# power_board.net
KiCad netlist of a schematic drawn in EAGLE
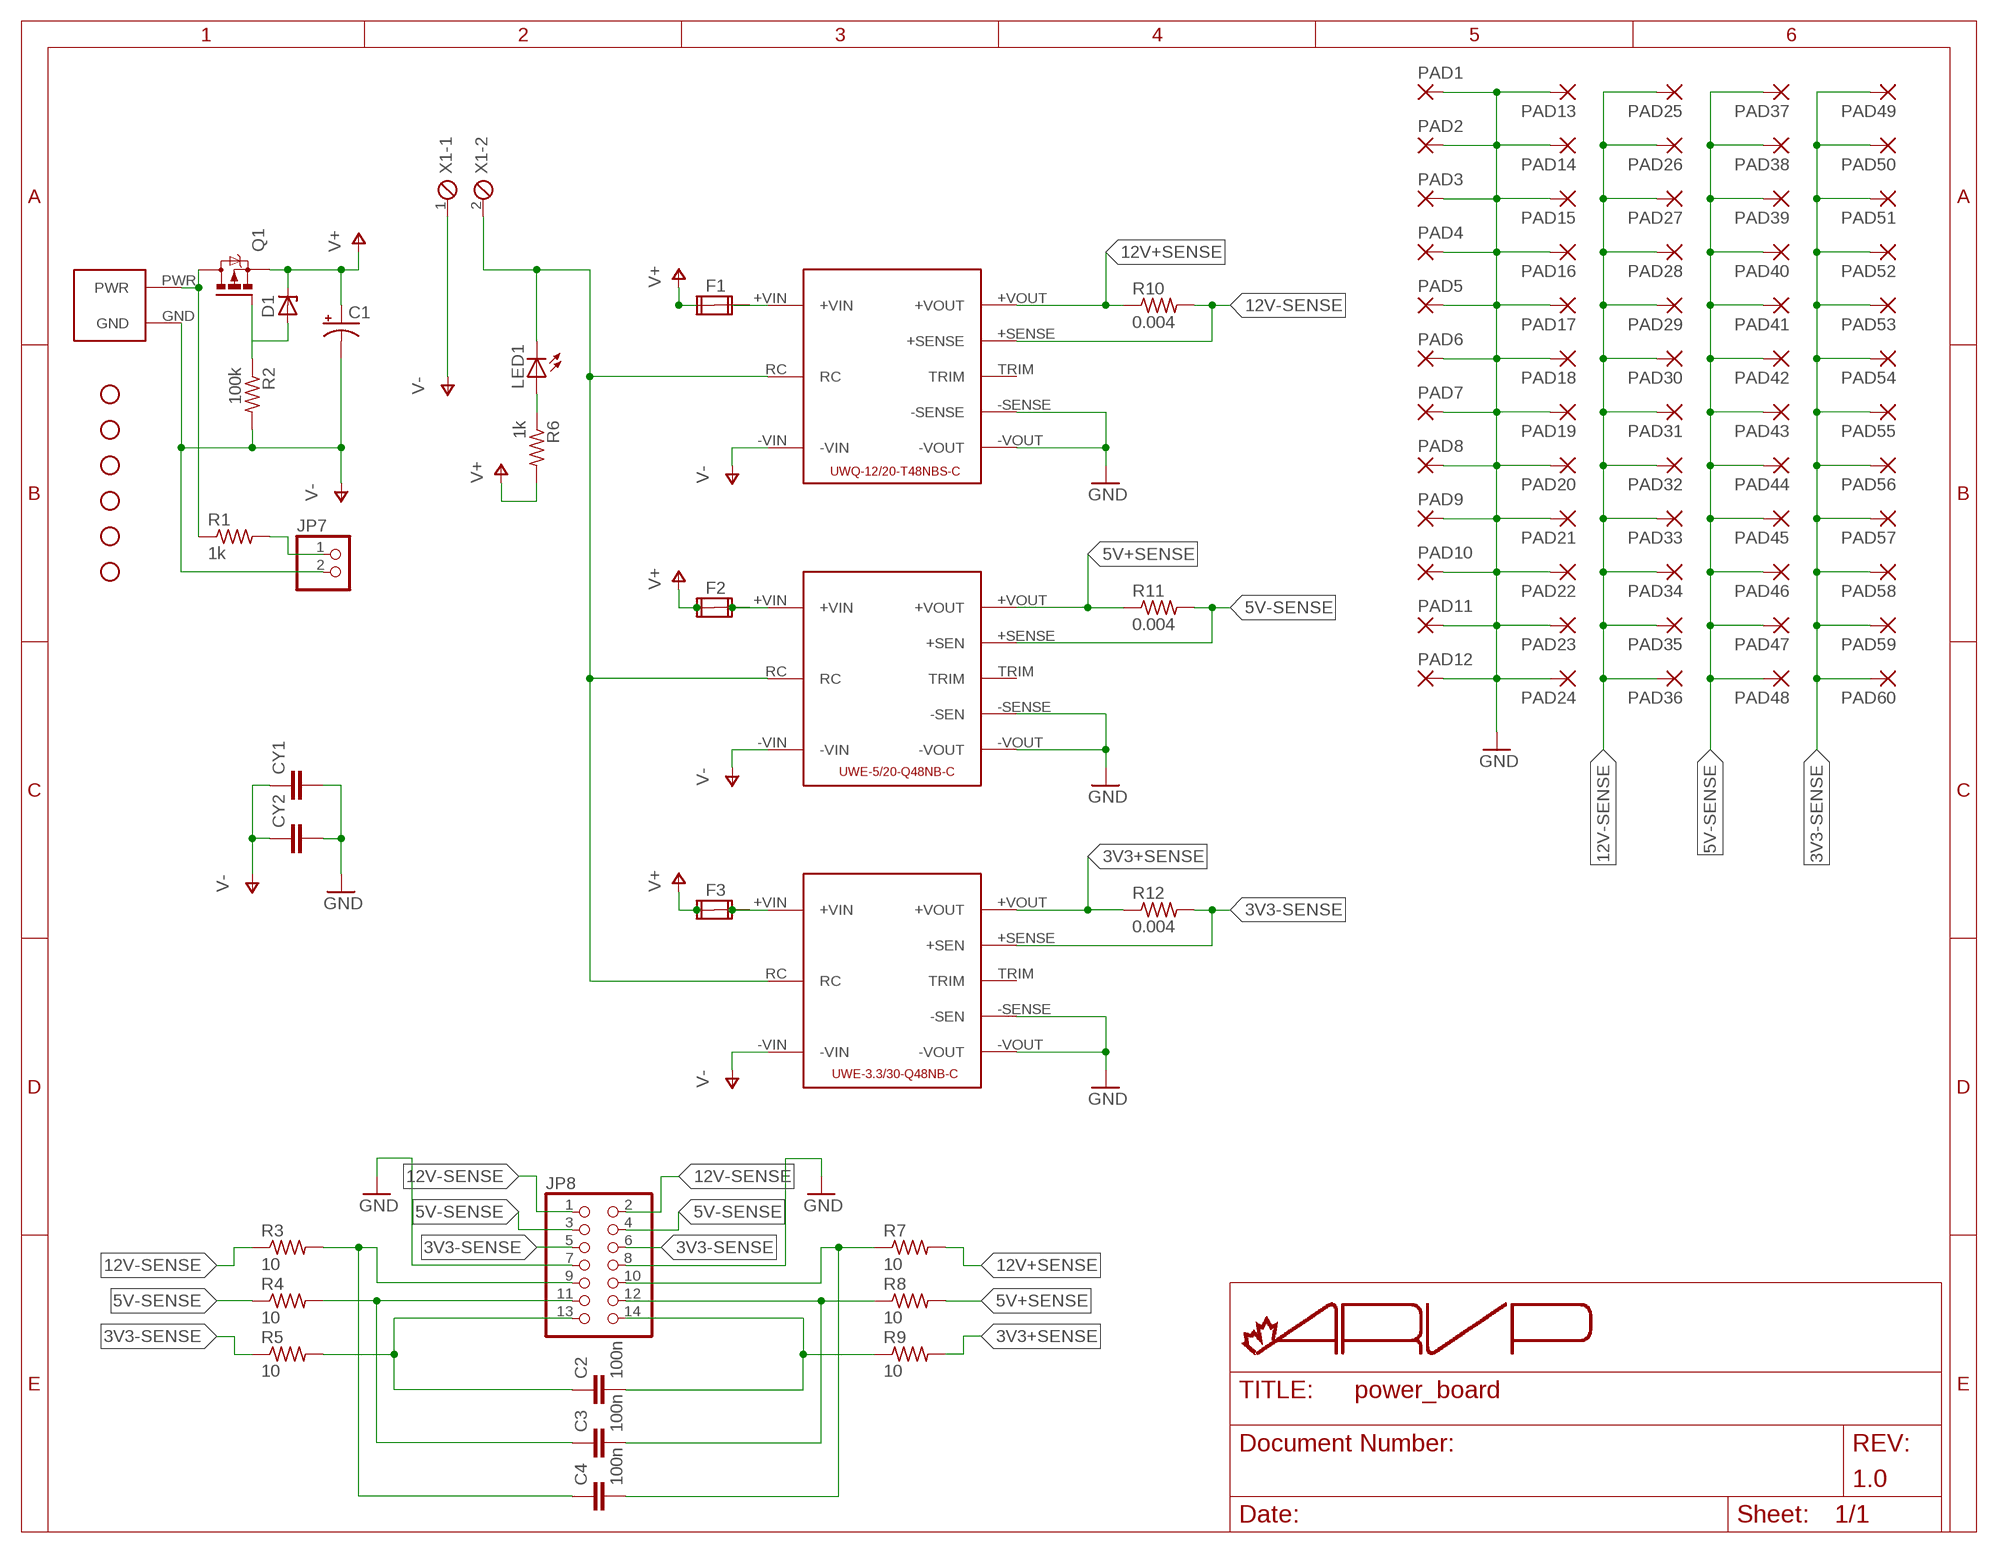
[diagram p0: schematic, sheet 1]

(export (version "E")
  (design (tool "Eeschema 10.0.6"))
  (components
    (comp (ref "C1")
      (value "CPOL-USE5-10.5")
      (footprint "eagle-import:E5-10,5")
      (libsource (lib "eagle-import") (part "CPOL-USE5-10.5"))
    )
    (comp (ref "C2")
      (value "100n")
      (footprint "eagle-import:C025-024X044")
      (libsource (lib "eagle-import") (part "C-EU025-024X044"))
    )
    (comp (ref "C3")
      (value "100n")
      (footprint "eagle-import:C025-024X044")
      (libsource (lib "eagle-import") (part "C-EU025-024X044"))
    )
    (comp (ref "C4")
      (value "100n")
      (footprint "eagle-import:C025-024X044")
      (libsource (lib "eagle-import") (part "C-EU025-024X044"))
    )
    (comp (ref "CY1")
      (value "CYYC7B5")
      (footprint "eagle-import:YC7B5")
      (libsource (lib "eagle-import") (part "CYYC7B5"))
    )
    (comp (ref "CY2")
      (value "CYYC7B5")
      (footprint "eagle-import:YC7B5")
      (libsource (lib "eagle-import") (part "CYYC7B5"))
    )
    (comp (ref "D1")
      (value "ZENER-DIODEDO35Z10")
      (footprint "eagle-import:DO35Z10")
      (libsource (lib "eagle-import") (part "ZENER-DIODEDO35Z10"))
    )
    (comp (ref "F1")
      (value "FUSE2P")
      (footprint "eagle-import:FUSE1")
      (libsource (lib "eagle-import") (part "FUSE2P"))
    )
    (comp (ref "F2")
      (value "FUSE2P")
      (footprint "eagle-import:FUSE1")
      (libsource (lib "eagle-import") (part "FUSE2P"))
    )
    (comp (ref "F3")
      (value "FUSE2P")
      (footprint "eagle-import:FUSE1")
      (libsource (lib "eagle-import") (part "FUSE2P"))
    )
    (comp (ref "JP1")
      (value "STAND-OFF")
      (footprint "eagle-import:STAND-OFF")
      (libsource (lib "eagle-import") (part "STAND-OFF"))
    )
    (comp (ref "JP2")
      (value "STAND-OFF")
      (footprint "eagle-import:STAND-OFF")
      (libsource (lib "eagle-import") (part "STAND-OFF"))
    )
    (comp (ref "JP3")
      (value "STAND-OFF")
      (footprint "eagle-import:STAND-OFF")
      (libsource (lib "eagle-import") (part "STAND-OFF"))
    )
    (comp (ref "JP4")
      (value "STAND-OFF")
      (footprint "eagle-import:STAND-OFF")
      (libsource (lib "eagle-import") (part "STAND-OFF"))
    )
    (comp (ref "JP5")
      (value "STAND-OFF")
      (footprint "eagle-import:STAND-OFF")
      (libsource (lib "eagle-import") (part "STAND-OFF"))
    )
    (comp (ref "JP6")
      (value "STAND-OFF")
      (footprint "eagle-import:STAND-OFF")
      (libsource (lib "eagle-import") (part "STAND-OFF"))
    )
    (comp (ref "JP7")
      (value "PINHD-1X2")
      (footprint "eagle-import:1X02")
      (libsource (lib "eagle-import") (part "PINHD-1X2"))
    )
    (comp (ref "JP8")
      (value "PINHD-2X7")
      (footprint "eagle-import:2X07")
      (libsource (lib "eagle-import") (part "PINHD-2X7"))
    )
    (comp (ref "LED1")
      (value "LED3MM")
      (footprint "eagle-import:LED3MM")
      (libsource (lib "eagle-import") (part "LED3MM"))
    )
    (comp (ref "P$1")
      (value "AND_PWR")
      (footprint "eagle-import:AND_PWR")
      (libsource (lib "eagle-import") (part "AND_PWR"))
    )
    (comp (ref "PAD1")
      (value "WIREPAD3,17/1,3")
      (footprint "eagle-import:3,17_1,3")
      (libsource (lib "eagle-import") (part "WIREPAD3,17/1,3"))
    )
    (comp (ref "PAD2")
      (value "WIREPAD3,17/1,3")
      (footprint "eagle-import:3,17_1,3")
      (libsource (lib "eagle-import") (part "WIREPAD3,17/1,3"))
    )
    (comp (ref "PAD3")
      (value "WIREPAD3,17/1,3")
      (footprint "eagle-import:3,17_1,3")
      (libsource (lib "eagle-import") (part "WIREPAD3,17/1,3"))
    )
    (comp (ref "PAD4")
      (value "WIREPAD3,17/1,3")
      (footprint "eagle-import:3,17_1,3")
      (libsource (lib "eagle-import") (part "WIREPAD3,17/1,3"))
    )
    (comp (ref "PAD5")
      (value "WIREPAD3,17/1,3")
      (footprint "eagle-import:3,17_1,3")
      (libsource (lib "eagle-import") (part "WIREPAD3,17/1,3"))
    )
    (comp (ref "PAD6")
      (value "WIREPAD3,17/1,3")
      (footprint "eagle-import:3,17_1,3")
      (libsource (lib "eagle-import") (part "WIREPAD3,17/1,3"))
    )
    (comp (ref "PAD7")
      (value "WIREPAD3,17/1,3")
      (footprint "eagle-import:3,17_1,3")
      (libsource (lib "eagle-import") (part "WIREPAD3,17/1,3"))
    )
    (comp (ref "PAD8")
      (value "WIREPAD3,17/1,3")
      (footprint "eagle-import:3,17_1,3")
      (libsource (lib "eagle-import") (part "WIREPAD3,17/1,3"))
    )
    (comp (ref "PAD9")
      (value "WIREPAD3,17/1,3")
      (footprint "eagle-import:3,17_1,3")
      (libsource (lib "eagle-import") (part "WIREPAD3,17/1,3"))
    )
    (comp (ref "PAD10")
      (value "WIREPAD3,17/1,3")
      (footprint "eagle-import:3,17_1,3")
      (libsource (lib "eagle-import") (part "WIREPAD3,17/1,3"))
    )
    (comp (ref "PAD11")
      (value "WIREPAD3,17/1,3")
      (footprint "eagle-import:3,17_1,3")
      (libsource (lib "eagle-import") (part "WIREPAD3,17/1,3"))
    )
    (comp (ref "PAD12")
      (value "WIREPAD3,17/1,3")
      (footprint "eagle-import:3,17_1,3")
      (libsource (lib "eagle-import") (part "WIREPAD3,17/1,3"))
    )
    (comp (ref "PAD13")
      (value "WIREPAD3,17/1,3")
      (footprint "eagle-import:3,17_1,3")
      (libsource (lib "eagle-import") (part "WIREPAD3,17/1,3"))
    )
    (comp (ref "PAD14")
      (value "WIREPAD3,17/1,3")
      (footprint "eagle-import:3,17_1,3")
      (libsource (lib "eagle-import") (part "WIREPAD3,17/1,3"))
    )
    (comp (ref "PAD15")
      (value "WIREPAD3,17/1,3")
      (footprint "eagle-import:3,17_1,3")
      (libsource (lib "eagle-import") (part "WIREPAD3,17/1,3"))
    )
    (comp (ref "PAD16")
      (value "WIREPAD3,17/1,3")
      (footprint "eagle-import:3,17_1,3")
      (libsource (lib "eagle-import") (part "WIREPAD3,17/1,3"))
    )
    (comp (ref "PAD17")
      (value "WIREPAD3,17/1,3")
      (footprint "eagle-import:3,17_1,3")
      (libsource (lib "eagle-import") (part "WIREPAD3,17/1,3"))
    )
    (comp (ref "PAD18")
      (value "WIREPAD3,17/1,3")
      (footprint "eagle-import:3,17_1,3")
      (libsource (lib "eagle-import") (part "WIREPAD3,17/1,3"))
    )
    (comp (ref "PAD19")
      (value "WIREPAD3,17/1,3")
      (footprint "eagle-import:3,17_1,3")
      (libsource (lib "eagle-import") (part "WIREPAD3,17/1,3"))
    )
    (comp (ref "PAD20")
      (value "WIREPAD3,17/1,3")
      (footprint "eagle-import:3,17_1,3")
      (libsource (lib "eagle-import") (part "WIREPAD3,17/1,3"))
    )
    (comp (ref "PAD21")
      (value "WIREPAD3,17/1,3")
      (footprint "eagle-import:3,17_1,3")
      (libsource (lib "eagle-import") (part "WIREPAD3,17/1,3"))
    )
    (comp (ref "PAD22")
      (value "WIREPAD3,17/1,3")
      (footprint "eagle-import:3,17_1,3")
      (libsource (lib "eagle-import") (part "WIREPAD3,17/1,3"))
    )
    (comp (ref "PAD23")
      (value "WIREPAD3,17/1,3")
      (footprint "eagle-import:3,17_1,3")
      (libsource (lib "eagle-import") (part "WIREPAD3,17/1,3"))
    )
    (comp (ref "PAD24")
      (value "WIREPAD3,17/1,3")
      (footprint "eagle-import:3,17_1,3")
      (libsource (lib "eagle-import") (part "WIREPAD3,17/1,3"))
    )
    (comp (ref "PAD25")
      (value "WIREPAD3,17/1,3")
      (footprint "eagle-import:3,17_1,3")
      (libsource (lib "eagle-import") (part "WIREPAD3,17/1,3"))
    )
    (comp (ref "PAD26")
      (value "WIREPAD3,17/1,3")
      (footprint "eagle-import:3,17_1,3")
      (libsource (lib "eagle-import") (part "WIREPAD3,17/1,3"))
    )
    (comp (ref "PAD27")
      (value "WIREPAD3,17/1,3")
      (footprint "eagle-import:3,17_1,3")
      (libsource (lib "eagle-import") (part "WIREPAD3,17/1,3"))
    )
    (comp (ref "PAD28")
      (value "WIREPAD3,17/1,3")
      (footprint "eagle-import:3,17_1,3")
      (libsource (lib "eagle-import") (part "WIREPAD3,17/1,3"))
    )
    (comp (ref "PAD29")
      (value "WIREPAD3,17/1,3")
      (footprint "eagle-import:3,17_1,3")
      (libsource (lib "eagle-import") (part "WIREPAD3,17/1,3"))
    )
    (comp (ref "PAD30")
      (value "WIREPAD3,17/1,3")
      (footprint "eagle-import:3,17_1,3")
      (libsource (lib "eagle-import") (part "WIREPAD3,17/1,3"))
    )
    (comp (ref "PAD31")
      (value "WIREPAD3,17/1,3")
      (footprint "eagle-import:3,17_1,3")
      (libsource (lib "eagle-import") (part "WIREPAD3,17/1,3"))
    )
    (comp (ref "PAD32")
      (value "WIREPAD3,17/1,3")
      (footprint "eagle-import:3,17_1,3")
      (libsource (lib "eagle-import") (part "WIREPAD3,17/1,3"))
    )
    (comp (ref "PAD33")
      (value "WIREPAD3,17/1,3")
      (footprint "eagle-import:3,17_1,3")
      (libsource (lib "eagle-import") (part "WIREPAD3,17/1,3"))
    )
    (comp (ref "PAD34")
      (value "WIREPAD3,17/1,3")
      (footprint "eagle-import:3,17_1,3")
      (libsource (lib "eagle-import") (part "WIREPAD3,17/1,3"))
    )
    (comp (ref "PAD35")
      (value "WIREPAD3,17/1,3")
      (footprint "eagle-import:3,17_1,3")
      (libsource (lib "eagle-import") (part "WIREPAD3,17/1,3"))
    )
    (comp (ref "PAD36")
      (value "WIREPAD3,17/1,3")
      (footprint "eagle-import:3,17_1,3")
      (libsource (lib "eagle-import") (part "WIREPAD3,17/1,3"))
    )
    (comp (ref "PAD37")
      (value "WIREPAD3,17/1,3")
      (footprint "eagle-import:3,17_1,3")
      (libsource (lib "eagle-import") (part "WIREPAD3,17/1,3"))
    )
    (comp (ref "PAD38")
      (value "WIREPAD3,17/1,3")
      (footprint "eagle-import:3,17_1,3")
      (libsource (lib "eagle-import") (part "WIREPAD3,17/1,3"))
    )
    (comp (ref "PAD39")
      (value "WIREPAD3,17/1,3")
      (footprint "eagle-import:3,17_1,3")
      (libsource (lib "eagle-import") (part "WIREPAD3,17/1,3"))
    )
    (comp (ref "PAD40")
      (value "WIREPAD3,17/1,3")
      (footprint "eagle-import:3,17_1,3")
      (libsource (lib "eagle-import") (part "WIREPAD3,17/1,3"))
    )
    (comp (ref "PAD41")
      (value "WIREPAD3,17/1,3")
      (footprint "eagle-import:3,17_1,3")
      (libsource (lib "eagle-import") (part "WIREPAD3,17/1,3"))
    )
    (comp (ref "PAD42")
      (value "WIREPAD3,17/1,3")
      (footprint "eagle-import:3,17_1,3")
      (libsource (lib "eagle-import") (part "WIREPAD3,17/1,3"))
    )
    (comp (ref "PAD43")
      (value "WIREPAD3,17/1,3")
      (footprint "eagle-import:3,17_1,3")
      (libsource (lib "eagle-import") (part "WIREPAD3,17/1,3"))
    )
    (comp (ref "PAD44")
      (value "WIREPAD3,17/1,3")
      (footprint "eagle-import:3,17_1,3")
      (libsource (lib "eagle-import") (part "WIREPAD3,17/1,3"))
    )
    (comp (ref "PAD45")
      (value "WIREPAD3,17/1,3")
      (footprint "eagle-import:3,17_1,3")
      (libsource (lib "eagle-import") (part "WIREPAD3,17/1,3"))
    )
    (comp (ref "PAD46")
      (value "WIREPAD3,17/1,3")
      (footprint "eagle-import:3,17_1,3")
      (libsource (lib "eagle-import") (part "WIREPAD3,17/1,3"))
    )
    (comp (ref "PAD47")
      (value "WIREPAD3,17/1,3")
      (footprint "eagle-import:3,17_1,3")
      (libsource (lib "eagle-import") (part "WIREPAD3,17/1,3"))
    )
    (comp (ref "PAD48")
      (value "WIREPAD3,17/1,3")
      (footprint "eagle-import:3,17_1,3")
      (libsource (lib "eagle-import") (part "WIREPAD3,17/1,3"))
    )
    (comp (ref "PAD49")
      (value "WIREPAD3,17/1,3")
      (footprint "eagle-import:3,17_1,3")
      (libsource (lib "eagle-import") (part "WIREPAD3,17/1,3"))
    )
    (comp (ref "PAD50")
      (value "WIREPAD3,17/1,3")
      (footprint "eagle-import:3,17_1,3")
      (libsource (lib "eagle-import") (part "WIREPAD3,17/1,3"))
    )
    (comp (ref "PAD51")
      (value "WIREPAD3,17/1,3")
      (footprint "eagle-import:3,17_1,3")
      (libsource (lib "eagle-import") (part "WIREPAD3,17/1,3"))
    )
    (comp (ref "PAD52")
      (value "WIREPAD3,17/1,3")
      (footprint "eagle-import:3,17_1,3")
      (libsource (lib "eagle-import") (part "WIREPAD3,17/1,3"))
    )
    (comp (ref "PAD53")
      (value "WIREPAD3,17/1,3")
      (footprint "eagle-import:3,17_1,3")
      (libsource (lib "eagle-import") (part "WIREPAD3,17/1,3"))
    )
    (comp (ref "PAD54")
      (value "WIREPAD3,17/1,3")
      (footprint "eagle-import:3,17_1,3")
      (libsource (lib "eagle-import") (part "WIREPAD3,17/1,3"))
    )
    (comp (ref "PAD55")
      (value "WIREPAD3,17/1,3")
      (footprint "eagle-import:3,17_1,3")
      (libsource (lib "eagle-import") (part "WIREPAD3,17/1,3"))
    )
    (comp (ref "PAD56")
      (value "WIREPAD3,17/1,3")
      (footprint "eagle-import:3,17_1,3")
      (libsource (lib "eagle-import") (part "WIREPAD3,17/1,3"))
    )
    (comp (ref "PAD57")
      (value "WIREPAD3,17/1,3")
      (footprint "eagle-import:3,17_1,3")
      (libsource (lib "eagle-import") (part "WIREPAD3,17/1,3"))
    )
    (comp (ref "PAD58")
      (value "WIREPAD3,17/1,3")
      (footprint "eagle-import:3,17_1,3")
      (libsource (lib "eagle-import") (part "WIREPAD3,17/1,3"))
    )
    (comp (ref "PAD59")
      (value "WIREPAD3,17/1,3")
      (footprint "eagle-import:3,17_1,3")
      (libsource (lib "eagle-import") (part "WIREPAD3,17/1,3"))
    )
    (comp (ref "PAD60")
      (value "WIREPAD3,17/1,3")
      (footprint "eagle-import:3,17_1,3")
      (libsource (lib "eagle-import") (part "WIREPAD3,17/1,3"))
    )
    (comp (ref "Q1")
      (value "IPP80P03P4L04AKSA1")
      (footprint "eagle-import:TO220BV")
      (libsource (lib "eagle-import") (part "IPP80P03P4L04AKSA1"))
    )
    (comp (ref "R1")
      (value "1k")
      (footprint "eagle-import:0204_7")
      (libsource (lib "eagle-import") (part "resistor_R-US_0204/7"))
    )
    (comp (ref "R2")
      (value "100k")
      (footprint "eagle-import:0204_7")
      (libsource (lib "eagle-import") (part "resistor_R-US_0204/7"))
    )
    (comp (ref "R3")
      (value "10")
      (footprint "eagle-import:0204_5")
      (libsource (lib "eagle-import") (part "R-US_0204/5"))
    )
    (comp (ref "R4")
      (value "10")
      (footprint "eagle-import:0204_5")
      (libsource (lib "eagle-import") (part "R-US_0204/5"))
    )
    (comp (ref "R5")
      (value "10")
      (footprint "eagle-import:0204_5")
      (libsource (lib "eagle-import") (part "R-US_0204/5"))
    )
    (comp (ref "R6")
      (value "1k")
      (footprint "eagle-import:0204_7")
      (libsource (lib "eagle-import") (part "resistor_R-US_0204/7"))
    )
    (comp (ref "R7")
      (value "10")
      (footprint "eagle-import:0204_5")
      (libsource (lib "eagle-import") (part "R-US_0204/5"))
    )
    (comp (ref "R8")
      (value "10")
      (footprint "eagle-import:0204_5")
      (libsource (lib "eagle-import") (part "R-US_0204/5"))
    )
    (comp (ref "R9")
      (value "10")
      (footprint "eagle-import:0204_5")
      (libsource (lib "eagle-import") (part "R-US_0204/5"))
    )
    (comp (ref "R10")
      (value "0.004")
      (footprint "eagle-import:0617_22")
      (libsource (lib "eagle-import") (part "R-US_0617/22"))
    )
    (comp (ref "R11")
      (value "0.004")
      (footprint "eagle-import:0617_22")
      (libsource (lib "eagle-import") (part "R-US_0617/22"))
    )
    (comp (ref "R12")
      (value "0.004")
      (footprint "eagle-import:0617_22")
      (libsource (lib "eagle-import") (part "R-US_0617/22"))
    )
    (comp (ref "U1")
      (value "UWQ-12/20-T48NBS-C")
      (footprint "eagle-import:UWQ-12_20-T48")
      (libsource (lib "eagle-import") (part "UWQ-12/20-T48NBS-C"))
    )
    (comp (ref "U2")
      (value "UWE-5/20-Q48NB-C")
      (footprint "eagle-import:UWE-100-120W")
      (libsource (lib "eagle-import") (part "UWE-5/20-Q48NB-C"))
    )
    (comp (ref "U3")
      (value "UWE-3.3/30-Q48NB-C")
      (footprint "eagle-import:UWE-100-120W")
      (libsource (lib "eagle-import") (part "UWE-3.3/30-Q48NB-C"))
    )
    (comp (ref "X1")
      (value "MPT2")
      (footprint "eagle-import:2POL254")
      (libsource (lib "eagle-import") (part "MPT2"))
    )
  )
  (nets
    (net (code "1") (name "3V3+SENSE") (class "Default")
      (node (ref "R12") (pin "1") (pinfunction "1_1") (pintype "passive"))
      (node (ref "R9") (pin "2") (pinfunction "2_2") (pintype "passive"))
      (node (ref "U3") (pin "+VOUT") (pinfunction "+VOUT_+VOUT") (pintype "power_in"))
    )
    (net (code "2") (name "3V3-SENSE") (class "Default")
      (node (ref "JP8") (pin "5") (pinfunction "5_5") (pintype "passive"))
      (node (ref "JP8") (pin "6") (pinfunction "6_6") (pintype "passive"))
      (node (ref "PAD49") (pin "1") (pinfunction "P_1") (pintype "passive"))
      (node (ref "PAD50") (pin "1") (pinfunction "P_1") (pintype "passive"))
      (node (ref "PAD51") (pin "1") (pinfunction "P_1") (pintype "passive"))
      (node (ref "PAD52") (pin "1") (pinfunction "P_1") (pintype "passive"))
      (node (ref "PAD53") (pin "1") (pinfunction "P_1") (pintype "passive"))
      (node (ref "PAD54") (pin "1") (pinfunction "P_1") (pintype "passive"))
      (node (ref "PAD55") (pin "1") (pinfunction "P_1") (pintype "passive"))
      (node (ref "PAD56") (pin "1") (pinfunction "P_1") (pintype "passive"))
      (node (ref "PAD57") (pin "1") (pinfunction "P_1") (pintype "passive"))
      (node (ref "PAD58") (pin "1") (pinfunction "P_1") (pintype "passive"))
      (node (ref "PAD59") (pin "1") (pinfunction "P_1") (pintype "passive"))
      (node (ref "PAD60") (pin "1") (pinfunction "P_1") (pintype "passive"))
      (node (ref "R12") (pin "2") (pinfunction "2_2") (pintype "passive"))
      (node (ref "R5") (pin "1") (pinfunction "1_1") (pintype "passive"))
      (node (ref "U3") (pin "+SENSE") (pinfunction "+SEN_+SENSE") (pintype "bidirectional"))
    )
    (net (code "3") (name "5V+SENSE") (class "Default")
      (node (ref "R11") (pin "1") (pinfunction "1_1") (pintype "passive"))
      (node (ref "R8") (pin "2") (pinfunction "2_2") (pintype "passive"))
      (node (ref "U2") (pin "+VOUT") (pinfunction "+VOUT_+VOUT") (pintype "power_in"))
    )
    (net (code "4") (name "5V-SENSE") (class "Default")
      (node (ref "JP8") (pin "3") (pinfunction "3_3") (pintype "passive"))
      (node (ref "JP8") (pin "4") (pinfunction "4_4") (pintype "passive"))
      (node (ref "PAD37") (pin "1") (pinfunction "P_1") (pintype "passive"))
      (node (ref "PAD38") (pin "1") (pinfunction "P_1") (pintype "passive"))
      (node (ref "PAD39") (pin "1") (pinfunction "P_1") (pintype "passive"))
      (node (ref "PAD40") (pin "1") (pinfunction "P_1") (pintype "passive"))
      (node (ref "PAD41") (pin "1") (pinfunction "P_1") (pintype "passive"))
      (node (ref "PAD42") (pin "1") (pinfunction "P_1") (pintype "passive"))
      (node (ref "PAD43") (pin "1") (pinfunction "P_1") (pintype "passive"))
      (node (ref "PAD44") (pin "1") (pinfunction "P_1") (pintype "passive"))
      (node (ref "PAD45") (pin "1") (pinfunction "P_1") (pintype "passive"))
      (node (ref "PAD46") (pin "1") (pinfunction "P_1") (pintype "passive"))
      (node (ref "PAD47") (pin "1") (pinfunction "P_1") (pintype "passive"))
      (node (ref "PAD48") (pin "1") (pinfunction "P_1") (pintype "passive"))
      (node (ref "R11") (pin "2") (pinfunction "2_2") (pintype "passive"))
      (node (ref "R4") (pin "1") (pinfunction "1_1") (pintype "passive"))
      (node (ref "U2") (pin "+SENSE") (pinfunction "+SEN_+SENSE") (pintype "bidirectional"))
    )
    (net (code "5") (name "12V+SENSE") (class "Default")
      (node (ref "R10") (pin "1") (pinfunction "1_1") (pintype "passive"))
      (node (ref "R7") (pin "2") (pinfunction "2_2") (pintype "passive"))
      (node (ref "U1") (pin "+VOUT") (pinfunction "+VOUT_+VOUT") (pintype "power_in"))
    )
    (net (code "6") (name "12V-SENSE") (class "Default")
      (node (ref "JP8") (pin "1") (pinfunction "1_1") (pintype "passive"))
      (node (ref "JP8") (pin "2") (pinfunction "2_2") (pintype "passive"))
      (node (ref "PAD25") (pin "1") (pinfunction "P_1") (pintype "passive"))
      (node (ref "PAD26") (pin "1") (pinfunction "P_1") (pintype "passive"))
      (node (ref "PAD27") (pin "1") (pinfunction "P_1") (pintype "passive"))
      (node (ref "PAD28") (pin "1") (pinfunction "P_1") (pintype "passive"))
      (node (ref "PAD29") (pin "1") (pinfunction "P_1") (pintype "passive"))
      (node (ref "PAD30") (pin "1") (pinfunction "P_1") (pintype "passive"))
      (node (ref "PAD31") (pin "1") (pinfunction "P_1") (pintype "passive"))
      (node (ref "PAD32") (pin "1") (pinfunction "P_1") (pintype "passive"))
      (node (ref "PAD33") (pin "1") (pinfunction "P_1") (pintype "passive"))
      (node (ref "PAD34") (pin "1") (pinfunction "P_1") (pintype "passive"))
      (node (ref "PAD35") (pin "1") (pinfunction "P_1") (pintype "passive"))
      (node (ref "PAD36") (pin "1") (pinfunction "P_1") (pintype "passive"))
      (node (ref "R10") (pin "2") (pinfunction "2_2") (pintype "passive"))
      (node (ref "R3") (pin "1") (pinfunction "1_1") (pintype "passive"))
      (node (ref "U1") (pin "+SENSE") (pinfunction "+SENSE_+SENSE") (pintype "bidirectional"))
    )
    (net (code "7") (name "GND") (class "Default")
      (node (ref "CY1") (pin "2") (pinfunction "2_2") (pintype "passive"))
      (node (ref "CY2") (pin "2") (pinfunction "2_2") (pintype "passive"))
      (node (ref "JP8") (pin "7") (pinfunction "7_7") (pintype "passive"))
      (node (ref "JP8") (pin "8") (pinfunction "8_8") (pintype "passive"))
      (node (ref "PAD1") (pin "1") (pinfunction "P_1") (pintype "passive"))
      (node (ref "PAD10") (pin "1") (pinfunction "P_1") (pintype "passive"))
      (node (ref "PAD11") (pin "1") (pinfunction "P_1") (pintype "passive"))
      (node (ref "PAD12") (pin "1") (pinfunction "P_1") (pintype "passive"))
      (node (ref "PAD13") (pin "1") (pinfunction "P_1") (pintype "passive"))
      (node (ref "PAD14") (pin "1") (pinfunction "P_1") (pintype "passive"))
      (node (ref "PAD15") (pin "1") (pinfunction "P_1") (pintype "passive"))
      (node (ref "PAD16") (pin "1") (pinfunction "P_1") (pintype "passive"))
      (node (ref "PAD17") (pin "1") (pinfunction "P_1") (pintype "passive"))
      (node (ref "PAD18") (pin "1") (pinfunction "P_1") (pintype "passive"))
      (node (ref "PAD19") (pin "1") (pinfunction "P_1") (pintype "passive"))
      (node (ref "PAD2") (pin "1") (pinfunction "P_1") (pintype "passive"))
      (node (ref "PAD20") (pin "1") (pinfunction "P_1") (pintype "passive"))
      (node (ref "PAD21") (pin "1") (pinfunction "P_1") (pintype "passive"))
      (node (ref "PAD22") (pin "1") (pinfunction "P_1") (pintype "passive"))
      (node (ref "PAD23") (pin "1") (pinfunction "P_1") (pintype "passive"))
      (node (ref "PAD24") (pin "1") (pinfunction "P_1") (pintype "passive"))
      (node (ref "PAD3") (pin "1") (pinfunction "P_1") (pintype "passive"))
      (node (ref "PAD4") (pin "1") (pinfunction "P_1") (pintype "passive"))
      (node (ref "PAD5") (pin "1") (pinfunction "P_1") (pintype "passive"))
      (node (ref "PAD6") (pin "1") (pinfunction "P_1") (pintype "passive"))
      (node (ref "PAD7") (pin "1") (pinfunction "P_1") (pintype "passive"))
      (node (ref "PAD8") (pin "1") (pinfunction "P_1") (pintype "passive"))
      (node (ref "PAD9") (pin "1") (pinfunction "P_1") (pintype "passive"))
      (node (ref "U1") (pin "-SENSE") (pinfunction "-SENSE_-SENSE") (pintype "bidirectional"))
      (node (ref "U1") (pin "-VOUT") (pinfunction "-VOUT_-VOUT") (pintype "power_in"))
      (node (ref "U2") (pin "-SENSE") (pinfunction "-SEN_-SENSE") (pintype "bidirectional"))
      (node (ref "U2") (pin "-VOUT") (pinfunction "-VOUT_-VOUT") (pintype "power_in"))
      (node (ref "U3") (pin "-SENSE") (pinfunction "-SEN_-SENSE") (pintype "bidirectional"))
      (node (ref "U3") (pin "-VOUT") (pinfunction "-VOUT_-VOUT") (pintype "power_in"))
    )
    (net (code "8") (name "Net-(C2-Pad1)") (class "Default")
      (node (ref "C2") (pin "1") (pinfunction "1_1") (pintype "passive"))
      (node (ref "JP8") (pin "13") (pinfunction "13_13") (pintype "passive"))
      (node (ref "R5") (pin "2") (pinfunction "2_2") (pintype "passive"))
    )
    (net (code "9") (name "Net-(C2-Pad2)") (class "Default")
      (node (ref "C2") (pin "2") (pinfunction "2_2") (pintype "passive"))
      (node (ref "JP8") (pin "14") (pinfunction "14_14") (pintype "passive"))
      (node (ref "R9") (pin "1") (pinfunction "1_1") (pintype "passive"))
    )
    (net (code "10") (name "Net-(C3-Pad1)") (class "Default")
      (node (ref "C3") (pin "1") (pinfunction "1_1") (pintype "passive"))
      (node (ref "JP8") (pin "11") (pinfunction "11_11") (pintype "passive"))
      (node (ref "R4") (pin "2") (pinfunction "2_2") (pintype "passive"))
    )
    (net (code "11") (name "Net-(C3-Pad2)") (class "Default")
      (node (ref "C3") (pin "2") (pinfunction "2_2") (pintype "passive"))
      (node (ref "JP8") (pin "12") (pinfunction "12_12") (pintype "passive"))
      (node (ref "R8") (pin "1") (pinfunction "1_1") (pintype "passive"))
    )
    (net (code "12") (name "Net-(C4-Pad1)") (class "Default")
      (node (ref "C4") (pin "1") (pinfunction "1_1") (pintype "passive"))
      (node (ref "JP8") (pin "9") (pinfunction "9_9") (pintype "passive"))
      (node (ref "R3") (pin "2") (pinfunction "2_2") (pintype "passive"))
    )
    (net (code "13") (name "Net-(C4-Pad2)") (class "Default")
      (node (ref "C4") (pin "2") (pinfunction "2_2") (pintype "passive"))
      (node (ref "JP8") (pin "10") (pinfunction "10_10") (pintype "passive"))
      (node (ref "R7") (pin "1") (pinfunction "1_1") (pintype "passive"))
    )
    (net (code "14") (name "Net-(D1-PadA)") (class "Default")
      (node (ref "D1") (pin "A") (pinfunction "A_A") (pintype "passive"))
      (node (ref "Q1") (pin "G") (pinfunction "G_G") (pintype "power_in"))
      (node (ref "R2") (pin "1") (pinfunction "1_1") (pintype "passive"))
    )
    (net (code "15") (name "Net-(F1-Pad2A)") (class "Default")
      (node (ref "F1") (pin "2A") (pinfunction "2A_2A") (pintype "passive"))
      (node (ref "F1") (pin "2B") (pinfunction "2B_2B") (pintype "passive"))
      (node (ref "U1") (pin "+VIN") (pinfunction "+VIN_+VIN") (pintype "power_in"))
    )
    (net (code "16") (name "Net-(F2-Pad2A)") (class "Default")
      (node (ref "F2") (pin "2A") (pinfunction "2A_2A") (pintype "passive"))
      (node (ref "F2") (pin "2B") (pinfunction "2B_2B") (pintype "passive"))
      (node (ref "U2") (pin "+VIN") (pinfunction "+VIN_+VIN") (pintype "power_in"))
    )
    (net (code "17") (name "Net-(F3-Pad2A)") (class "Default")
      (node (ref "F3") (pin "2A") (pinfunction "2A_2A") (pintype "passive"))
      (node (ref "F3") (pin "2B") (pinfunction "2B_2B") (pintype "passive"))
      (node (ref "U3") (pin "+VIN") (pinfunction "+VIN_+VIN") (pintype "power_in"))
    )
    (net (code "18") (name "Net-(JP7-Pad1)") (class "Default")
      (node (ref "JP7") (pin "1") (pinfunction "1_1") (pintype "passive"))
      (node (ref "R1") (pin "2") (pinfunction "2_2") (pintype "passive"))
    )
    (net (code "19") (name "Net-(LED1-C)") (class "Default")
      (node (ref "LED1") (pin "K") (pinfunction "C_K") (pintype "passive"))
      (node (ref "U1") (pin "RC") (pinfunction "RC_RC") (pintype "bidirectional"))
      (node (ref "U2") (pin "RC") (pinfunction "RC_RC") (pintype "bidirectional"))
      (node (ref "U3") (pin "RC") (pinfunction "RC_RC") (pintype "bidirectional"))
      (node (ref "X1") (pin "2") (pinfunction "1_2") (pintype "passive"))
    )
    (net (code "20") (name "Net-(LED1-PadA)") (class "Default")
      (node (ref "LED1") (pin "A") (pinfunction "A_A") (pintype "passive"))
      (node (ref "R6") (pin "1") (pinfunction "1_1") (pintype "passive"))
    )
    (net (code "21") (name "Net-(P$1-PadPWR)") (class "Default")
      (node (ref "P$1") (pin "PWR") (pinfunction "PWR_PWR") (pintype "bidirectional"))
      (node (ref "Q1") (pin "D") (pinfunction "D_D") (pintype "power_in"))
      (node (ref "R1") (pin "1") (pinfunction "1_1") (pintype "passive"))
    )
    (net (code "22") (name "V+") (class "Default")
      (node (ref "C1") (pin "+") (pinfunction "+_+") (pintype "passive"))
      (node (ref "D1") (pin "C") (pinfunction "C_C") (pintype "passive"))
      (node (ref "F1") (pin "1A") (pinfunction "1A_1A") (pintype "passive"))
      (node (ref "F1") (pin "1B") (pinfunction "1B_1B") (pintype "passive"))
      (node (ref "F2") (pin "1A") (pinfunction "1A_1A") (pintype "passive"))
      (node (ref "F2") (pin "1B") (pinfunction "1B_1B") (pintype "passive"))
      (node (ref "F3") (pin "1A") (pinfunction "1A_1A") (pintype "passive"))
      (node (ref "F3") (pin "1B") (pinfunction "1B_1B") (pintype "passive"))
      (node (ref "Q1") (pin "S") (pinfunction "S_S") (pintype "power_in"))
      (node (ref "R6") (pin "2") (pinfunction "2_2") (pintype "passive"))
    )
    (net (code "23") (name "V-") (class "Default")
      (node (ref "C1") (pin "-") (pinfunction "-_-") (pintype "passive"))
      (node (ref "CY1") (pin "1") (pinfunction "1_1") (pintype "passive"))
      (node (ref "CY2") (pin "1") (pinfunction "1_1") (pintype "passive"))
      (node (ref "JP7") (pin "2") (pinfunction "2_2") (pintype "passive"))
      (node (ref "P$1") (pin "GND") (pinfunction "GND_GND") (pintype "bidirectional"))
      (node (ref "R2") (pin "2") (pinfunction "2_2") (pintype "passive"))
      (node (ref "U1") (pin "-VIN") (pinfunction "-VIN_-VIN") (pintype "power_in"))
      (node (ref "U2") (pin "-VIN") (pinfunction "-VIN_-VIN") (pintype "power_in"))
      (node (ref "U3") (pin "-VIN") (pinfunction "-VIN_-VIN") (pintype "power_in"))
      (node (ref "X1") (pin "1") (pinfunction "1_1") (pintype "passive"))
    )
    (net (code "24") (name "unconnected-(U1-PadTRIM)") (class "Default")
      (node (ref "U1") (pin "TRIM") (pinfunction "TRIM_TRIM") (pintype "bidirectional"))
    )
    (net (code "25") (name "unconnected-(U2-PadTRIM)") (class "Default")
      (node (ref "U2") (pin "TRIM") (pinfunction "TRIM_TRIM") (pintype "bidirectional"))
    )
    (net (code "26") (name "unconnected-(U3-PadTRIM)") (class "Default")
      (node (ref "U3") (pin "TRIM") (pinfunction "TRIM_TRIM") (pintype "bidirectional"))
    )
  )
)
